# Sheet1.net
KiCad netlist of a schematic drawn in Altium Designer
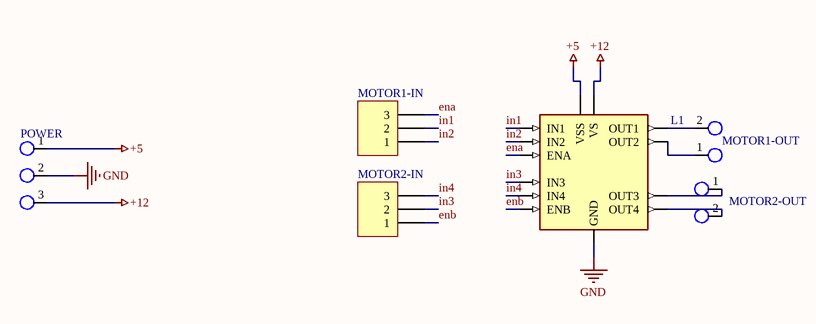
[diagram p0: Sheet1.SchDoc]

(export (version "E")
  (design (tool "Eeschema 10.0.6"))
  (components
    (comp (ref "L1") (value "L293D") (footprint "L293D") (libsource (lib "Schlib1") (part "L293D")))
    (comp (ref "MOTOR1-IN")
      (value "~")
      (footprint "HDR1X3")
      (description "Header, 3-Pin")
      (fields (field (name "PUBLISHER") "Altium Limited"))
      (libsource (lib "Miscellaneous Connectors") (part "Header 3"))
    )
    (comp (ref "MOTOR1-OUT")
      (value "~")
      (footprint "AK300/2")
      (fields (field (name "MP") "AK300/3") (field (name "MF") "Altech"))
      (libsource (lib "Schlib1") (part "AK300/2"))
    )
    (comp (ref "MOTOR2-IN")
      (value "~")
      (footprint "HDR1X3")
      (description "Header, 3-Pin")
      (fields (field (name "PUBLISHER") "Altium Limited"))
      (libsource (lib "Miscellaneous Connectors") (part "Header 3"))
    )
    (comp (ref "MOTOR2-OUT")
      (value "~")
      (footprint "AK300/2")
      (fields (field (name "MP") "AK300/3") (field (name "MF") "Altech"))
      (libsource (lib "Schlib1") (part "AK300/2"))
    )
    (comp (ref "POWER")
      (value "~")
      (footprint "AK300/3")
      (fields (field (name "MP") "AK300/3") (field (name "MF") "Altech"))
      (libsource (lib "Schlib1") (part "AK300/3"))
    )
  )
  (nets
    (net (code "1") (name "+5") (class "Default")
      (node (ref "L1") (pin "VSS") (pinfunction "VSS_VSS") (pintype "passive"))
      (node (ref "POWER") (pin "1") (pinfunction "KL_1") (pintype "passive"))
    )
    (net (code "2") (name "+12") (class "Default")
      (node (ref "L1") (pin "VS") (pinfunction "VS_VS") (pintype "passive"))
      (node (ref "POWER") (pin "3") (pinfunction "KL_3") (pintype "passive"))
    )
    (net (code "3") (name "/ena") (class "Default")
      (node (ref "L1") (pin "ENA") (pinfunction "ENA_ENA") (pintype "input"))
      (node (ref "MOTOR1-IN") (pin "3") (pinfunction "3_3") (pintype "passive"))
    )
    (net (code "4") (name "/enb") (class "Default")
      (node (ref "L1") (pin "ENB") (pinfunction "ENB_ENB") (pintype "input"))
      (node (ref "MOTOR2-IN") (pin "1") (pinfunction "1_1") (pintype "passive"))
    )
    (net (code "5") (name "/in1") (class "Default")
      (node (ref "L1") (pin "IN1") (pinfunction "IN1_IN1") (pintype "input"))
      (node (ref "MOTOR1-IN") (pin "2") (pinfunction "2_2") (pintype "passive"))
    )
    (net (code "6") (name "/in2") (class "Default")
      (node (ref "L1") (pin "IN2") (pinfunction "IN2_IN2") (pintype "input"))
      (node (ref "MOTOR1-IN") (pin "1") (pinfunction "1_1") (pintype "passive"))
    )
    (net (code "7") (name "/in3") (class "Default")
      (node (ref "L1") (pin "IN3") (pinfunction "IN3_IN3") (pintype "input"))
      (node (ref "MOTOR2-IN") (pin "2") (pinfunction "2_2") (pintype "passive"))
    )
    (net (code "8") (name "/in4") (class "Default")
      (node (ref "L1") (pin "IN4") (pinfunction "IN4_IN4") (pintype "input"))
      (node (ref "MOTOR2-IN") (pin "3") (pinfunction "3_3") (pintype "passive"))
    )
    (net (code "9") (name "GND") (class "Default")
      (node (ref "L1") (pin "GND") (pinfunction "GND_GND") (pintype "passive"))
      (node (ref "POWER") (pin "2") (pinfunction "KL_2") (pintype "passive"))
    )
    (net (code "10") (name "Net-(L1-PadOUT1)") (class "Default")
      (node (ref "L1") (pin "OUT1") (pinfunction "OUT1_OUT1") (pintype "output"))
      (node (ref "MOTOR1-OUT") (pin "2") (pinfunction "KL_2") (pintype "passive"))
    )
    (net (code "11") (name "Net-(L1-PadOUT2)") (class "Default")
      (node (ref "L1") (pin "OUT2") (pinfunction "OUT2_OUT2") (pintype "output"))
      (node (ref "MOTOR1-OUT") (pin "1") (pinfunction "KL_1") (pintype "passive"))
    )
    (net (code "12") (name "Net-(L1-PadOUT3)") (class "Default")
      (node (ref "L1") (pin "OUT3") (pinfunction "OUT3_OUT3") (pintype "output"))
      (node (ref "MOTOR2-OUT") (pin "1") (pinfunction "KL_1") (pintype "passive"))
    )
    (net (code "13") (name "Net-(L1-PadOUT4)") (class "Default")
      (node (ref "L1") (pin "OUT4") (pinfunction "OUT4_OUT4") (pintype "output"))
      (node (ref "MOTOR2-OUT") (pin "2") (pinfunction "KL_2") (pintype "passive"))
    )
  )
)
